# psnoise.net
KiCad netlist of a schematic drawn in EAGLE
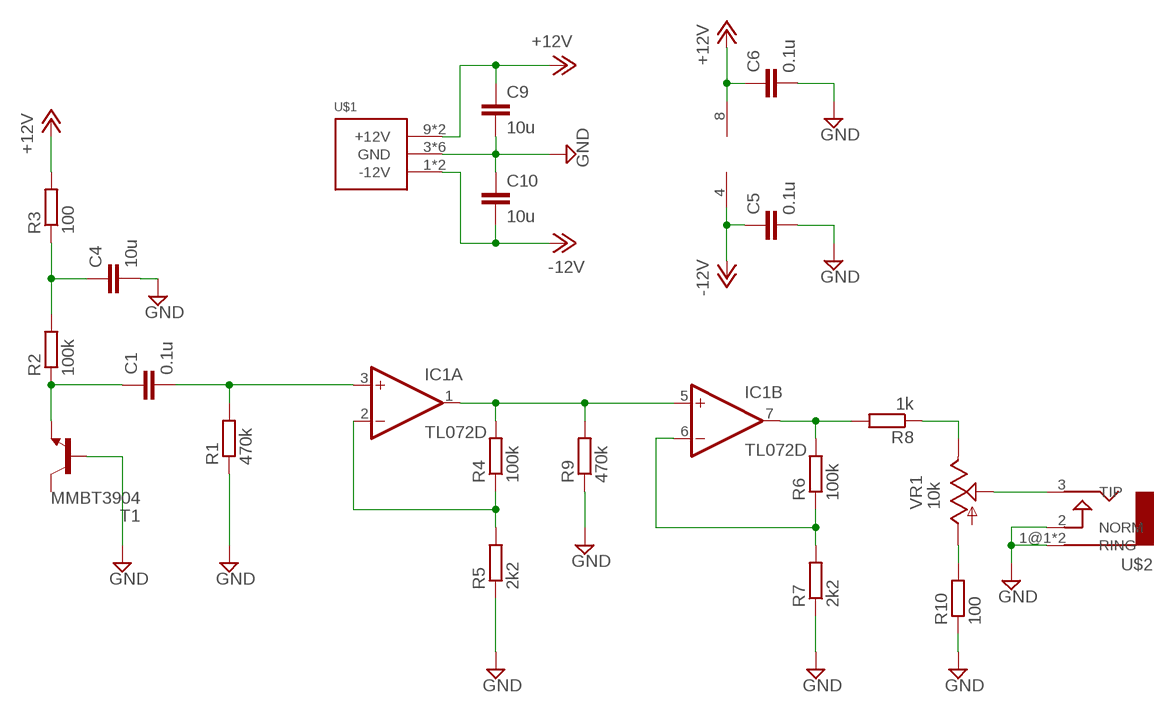
[diagram p0: schematic, sheet 1]

(export (version "E")
  (design (tool "Eeschema 10.0.6"))
  (components
    (comp (ref "C1")
      (value "0.1u")
      (footprint "eagle-import:C0805")
      (libsource (lib "eagle-import") (part "C-EUC0805"))
    )
    (comp (ref "C4")
      (value "10u")
      (footprint "eagle-import:C0805")
      (libsource (lib "eagle-import") (part "C-EUC0805"))
    )
    (comp (ref "C5")
      (value "0.1u")
      (footprint "eagle-import:C0805")
      (libsource (lib "eagle-import") (part "C-EUC0805"))
    )
    (comp (ref "C6")
      (value "0.1u")
      (footprint "eagle-import:C0805")
      (libsource (lib "eagle-import") (part "C-EUC0805"))
    )
    (comp (ref "C9")
      (value "10u")
      (footprint "eagle-import:C0805")
      (libsource (lib "eagle-import") (part "C-EUC0805"))
    )
    (comp (ref "C10")
      (value "10u")
      (footprint "eagle-import:C0805")
      (libsource (lib "eagle-import") (part "C-EUC0805"))
    )
    (comp (ref "IC1")
      (value "TL072D")
      (footprint "eagle-import:SO08")
      (libsource (lib "eagle-import") (part "TL072D"))
    )
    (comp (ref "R1")
      (value "470k")
      (footprint "eagle-import:R0805")
      (libsource (lib "eagle-import") (part "R-EU_R0805"))
    )
    (comp (ref "R2")
      (value "100k")
      (footprint "eagle-import:R0805")
      (libsource (lib "eagle-import") (part "R-EU_R0805"))
    )
    (comp (ref "R3")
      (value "100")
      (footprint "eagle-import:R0805")
      (libsource (lib "eagle-import") (part "R-EU_R0805"))
    )
    (comp (ref "R4")
      (value "100k")
      (footprint "eagle-import:R0805")
      (libsource (lib "eagle-import") (part "R-EU_R0805"))
    )
    (comp (ref "R5")
      (value "2k2")
      (footprint "eagle-import:R0805")
      (libsource (lib "eagle-import") (part "R-EU_R0805"))
    )
    (comp (ref "R6")
      (value "100k")
      (footprint "eagle-import:R0805")
      (libsource (lib "eagle-import") (part "R-EU_R0805"))
    )
    (comp (ref "R7")
      (value "2k2")
      (footprint "eagle-import:R0805")
      (libsource (lib "eagle-import") (part "R-EU_R0805"))
    )
    (comp (ref "R8")
      (value "1k")
      (footprint "eagle-import:R0805")
      (libsource (lib "eagle-import") (part "R-EU_R0805"))
    )
    (comp (ref "R9")
      (value "470k")
      (footprint "eagle-import:R0805")
      (libsource (lib "eagle-import") (part "R-EU_R0805"))
    )
    (comp (ref "R10")
      (value "100")
      (footprint "eagle-import:R0805")
      (libsource (lib "eagle-import") (part "R-EU_R0805"))
    )
    (comp (ref "T1")
      (value "MMBT3904")
      (footprint "eagle-import:SOT23-BEC")
      (libsource (lib "eagle-import") (part "-NPN-SOT23-BECMMBT3904LT1"))
    )
    (comp (ref "U$1")
      (value "POWER_SIMPLE10")
      (footprint "eagle-import:POWER_10")
      (libsource (lib "eagle-import") (part "POWER_SIMPLE10"))
    )
    (comp (ref "U$2")
      (value "AUDIO-JACKERTHENVAR")
      (footprint "eagle-import:ERTHENVAR-JACK")
      (libsource (lib "eagle-import") (part "AUDIO-JACKERTHENVAR"))
    )
    (comp (ref "VR1")
      (value "10k")
      (footprint "eagle-import:9MM_SNAP-IN_POT")
      (libsource (lib "eagle-import") (part "9MM_SNAP-IN_POT_"))
    )
  )
  (nets
    (net (code "1") (name "+12V") (class "Default")
      (node (ref "C6") (pin "1") (pinfunction "1_1") (pintype "passive"))
      (node (ref "C9") (pin "1") (pinfunction "1_1") (pintype "passive"))
      (node (ref "IC1") (pin "8") (pinfunction "V+_8") (pintype "power_in"))
      (node (ref "R3") (pin "2") (pinfunction "2_2") (pintype "passive"))
      (node (ref "U$1") (pin "10") (pinfunction "+12V_10") (pintype "bidirectional"))
      (node (ref "U$1") (pin "9") (pinfunction "+12V_9") (pintype "bidirectional"))
    )
    (net (code "2") (name "-12V") (class "Default")
      (node (ref "C10") (pin "2") (pinfunction "2_2") (pintype "passive"))
      (node (ref "C5") (pin "1") (pinfunction "1_1") (pintype "passive"))
      (node (ref "IC1") (pin "4") (pinfunction "V-_4") (pintype "power_in"))
      (node (ref "U$1") (pin "1") (pinfunction "-12V_1") (pintype "bidirectional"))
      (node (ref "U$1") (pin "2") (pinfunction "-12V_2") (pintype "bidirectional"))
    )
    (net (code "3") (name "GND") (class "Default")
      (node (ref "C10") (pin "1") (pinfunction "1_1") (pintype "passive"))
      (node (ref "C4") (pin "2") (pinfunction "2_2") (pintype "passive"))
      (node (ref "C5") (pin "2") (pinfunction "2_2") (pintype "passive"))
      (node (ref "C6") (pin "2") (pinfunction "2_2") (pintype "passive"))
      (node (ref "C9") (pin "2") (pinfunction "2_2") (pintype "passive"))
      (node (ref "R1") (pin "1") (pinfunction "1_1") (pintype "passive"))
      (node (ref "R10") (pin "1") (pinfunction "1_1") (pintype "passive"))
      (node (ref "R5") (pin "1") (pinfunction "1_1") (pintype "passive"))
      (node (ref "R7") (pin "1") (pinfunction "1_1") (pintype "passive"))
      (node (ref "R9") (pin "1") (pinfunction "1_1") (pintype "passive"))
      (node (ref "T1") (pin "B") (pinfunction "B_B") (pintype "passive"))
      (node (ref "U$1") (pin "3") (pinfunction "GND_3") (pintype "bidirectional"))
      (node (ref "U$1") (pin "4") (pinfunction "GND_4") (pintype "bidirectional"))
      (node (ref "U$1") (pin "5") (pinfunction "GND_5") (pintype "bidirectional"))
      (node (ref "U$1") (pin "6") (pinfunction "GND_6") (pintype "bidirectional"))
      (node (ref "U$1") (pin "7") (pinfunction "GND_7") (pintype "bidirectional"))
      (node (ref "U$1") (pin "8") (pinfunction "GND_8") (pintype "bidirectional"))
      (node (ref "U$2") (pin "1@1") (pinfunction "RING_1@1") (pintype "bidirectional"))
      (node (ref "U$2") (pin "1@2") (pinfunction "RING_1@2") (pintype "bidirectional"))
      (node (ref "U$2") (pin "2") (pinfunction "NORM_2") (pintype "bidirectional"))
    )
    (net (code "4") (name "Net-(C1-Pad1)") (class "Default")
      (node (ref "C1") (pin "1") (pinfunction "1_1") (pintype "passive"))
      (node (ref "R2") (pin "1") (pinfunction "1_1") (pintype "passive"))
      (node (ref "T1") (pin "E") (pinfunction "E_E") (pintype "passive"))
    )
    (net (code "5") (name "Net-(C4-Pad1)") (class "Default")
      (node (ref "C4") (pin "1") (pinfunction "1_1") (pintype "passive"))
      (node (ref "R2") (pin "2") (pinfunction "2_2") (pintype "passive"))
      (node (ref "R3") (pin "1") (pinfunction "1_1") (pintype "passive"))
    )
    (net (code "6") (name "Net-(IC1A-+IN)") (class "Default")
      (node (ref "C1") (pin "2") (pinfunction "2_2") (pintype "passive"))
      (node (ref "IC1") (pin "3") (pinfunction "+IN_3") (pintype "input"))
      (node (ref "R1") (pin "2") (pinfunction "2_2") (pintype "passive"))
    )
    (net (code "7") (name "Net-(IC1A--IN)") (class "Default")
      (node (ref "IC1") (pin "2") (pinfunction "-IN_2") (pintype "input"))
      (node (ref "R4") (pin "1") (pinfunction "1_1") (pintype "passive"))
      (node (ref "R5") (pin "2") (pinfunction "2_2") (pintype "passive"))
    )
    (net (code "8") (name "Net-(IC1A-OUT)") (class "Default")
      (node (ref "IC1") (pin "1") (pinfunction "OUT_1") (pintype "output"))
      (node (ref "IC1") (pin "5") (pinfunction "+IN_5") (pintype "input"))
      (node (ref "R4") (pin "2") (pinfunction "2_2") (pintype "passive"))
      (node (ref "R9") (pin "2") (pinfunction "2_2") (pintype "passive"))
    )
    (net (code "9") (name "Net-(IC1B--IN)") (class "Default")
      (node (ref "IC1") (pin "6") (pinfunction "-IN_6") (pintype "input"))
      (node (ref "R6") (pin "1") (pinfunction "1_1") (pintype "passive"))
      (node (ref "R7") (pin "2") (pinfunction "2_2") (pintype "passive"))
    )
    (net (code "10") (name "Net-(IC1B-OUT)") (class "Default")
      (node (ref "IC1") (pin "7") (pinfunction "OUT_7") (pintype "output"))
      (node (ref "R6") (pin "2") (pinfunction "2_2") (pintype "passive"))
      (node (ref "R8") (pin "2") (pinfunction "2_2") (pintype "passive"))
    )
    (net (code "11") (name "Net-(U$2-TIP)") (class "Default")
      (node (ref "U$2") (pin "3") (pinfunction "TIP_3") (pintype "bidirectional"))
      (node (ref "VR1") (pin "2") (pinfunction "S_2") (pintype "passive"))
    )
    (net (code "12") (name "Net-(VR1-A)") (class "Default")
      (node (ref "R10") (pin "2") (pinfunction "2_2") (pintype "passive"))
      (node (ref "VR1") (pin "1") (pinfunction "A_1") (pintype "passive"))
    )
    (net (code "13") (name "Net-(VR1-E)") (class "Default")
      (node (ref "R8") (pin "1") (pinfunction "1_1") (pintype "passive"))
      (node (ref "VR1") (pin "3") (pinfunction "E_3") (pintype "passive"))
    )
    (net (code "14") (name "unconnected-(T1-PadC)") (class "Default")
      (node (ref "T1") (pin "C") (pinfunction "C_C") (pintype "passive"))
    )
  )
)
